# Logic_Module_-_Power_V7_2.net
KiCad netlist of a schematic drawn in EAGLE
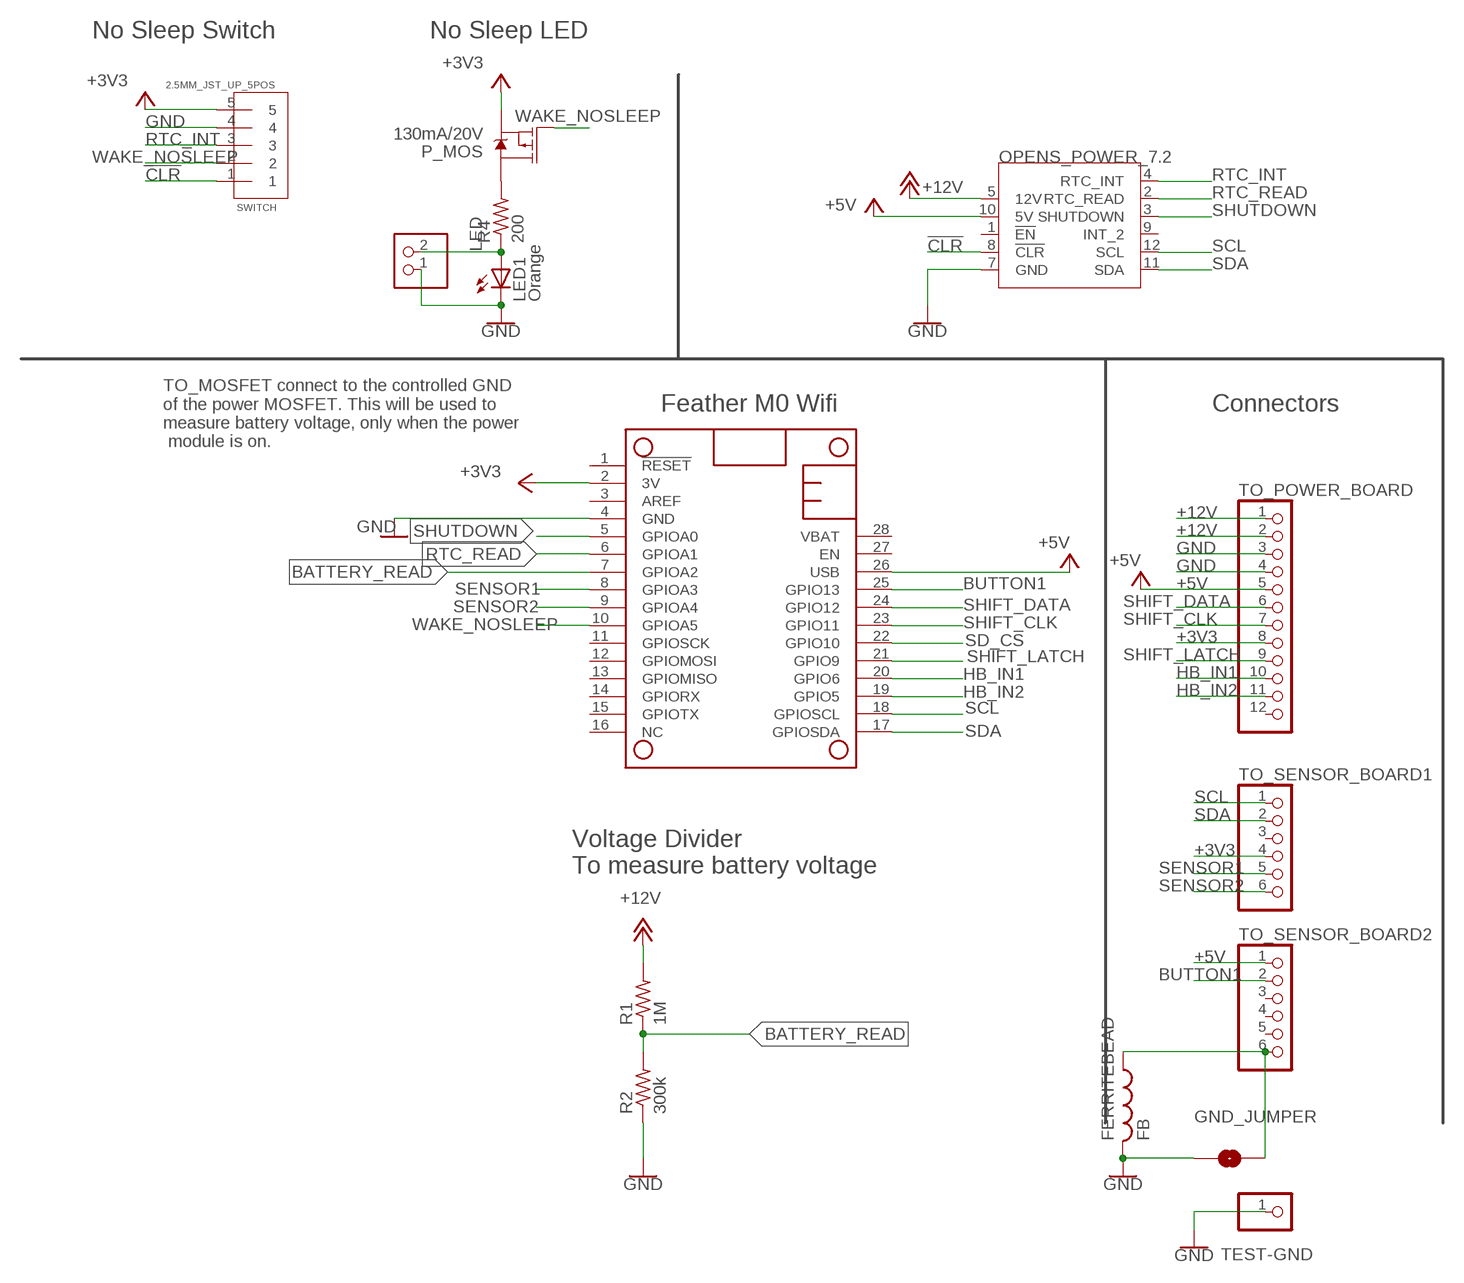
[diagram p0: schematic, sheet 1]

(export (version "E")
  (design (tool "Eeschema 10.0.6"))
  (components
    (comp (ref "FERRITEBEAD")
      (value "FB")
      (footprint "eagle-import:FB")
      (libsource (lib "eagle-import") (part "FB"))
    )
    (comp (ref "GND_JUMPER")
      (value "JUMPER-SMT_2_NO_NO-SILK")
      (footprint "eagle-import:SMT-JUMPER_2_NO_NO-SILK")
      (libsource (lib "eagle-import") (part "JUMPER-SMT_2_NO_NO-SILK"))
    )
    (comp (ref "LED")
      (value "2.5MM_JST_UP_2POS")
      (footprint "eagle-import:JST_2POS_2.5MM_UP")
      (libsource (lib "eagle-import") (part "2.5MM_JST_UP_2POS"))
    )
    (comp (ref "LED1")
      (value "Orange")
      (footprint "eagle-import:LED3MM")
      (libsource (lib "eagle-import") (part "LED3MM"))
    )
    (comp (ref "MS1")
      (value "FEATHERWING")
      (footprint "eagle-import:FEATHERWING")
      (libsource (lib "eagle-import") (part "FEATHERWING"))
    )
    (comp (ref "P_MOS")
      (value "130mA/20V")
      (footprint "eagle-import:SOT23-3")
      (libsource (lib "eagle-import") (part "MOSFET_PCH-IRLML2244"))
    )
    (comp (ref "R1")
      (value "1M")
      (footprint "eagle-import:R1206")
      (libsource (lib "eagle-import") (part "R-US_R1206"))
    )
    (comp (ref "R2")
      (value "300k")
      (footprint "eagle-import:R1206")
      (libsource (lib "eagle-import") (part "R-US_R1206"))
    )
    (comp (ref "R4")
      (value "200")
      (footprint "eagle-import:0204_7")
      (libsource (lib "eagle-import") (part "R-US_0204/7"))
    )
    (comp (ref "SWITCH")
      (value "2.5MM_JST_UP_5POS")
      (footprint "eagle-import:JST_5POS_2.5MM_UP")
      (libsource (lib "eagle-import") (part "2.5MM_JST_UP_5POS"))
    )
    (comp (ref "TEST-GND")
      (value "PINHD-1X1")
      (footprint "eagle-import:1X01")
      (libsource (lib "eagle-import") (part "PINHD-1X1"))
    )
    (comp (ref "TO_POWER_BOARD")
      (value "PINHD-1X12")
      (footprint "eagle-import:1X12")
      (libsource (lib "eagle-import") (part "PINHD-1X12"))
    )
    (comp (ref "TO_SENSOR_BOARD1")
      (value "PINHD-1X6CB")
      (footprint "eagle-import:1X06-CLEANBIG")
      (libsource (lib "eagle-import") (part "PINHD-1X6CB"))
    )
    (comp (ref "TO_SENSOR_BOARD2")
      (value "PINHD-1X6CB")
      (footprint "eagle-import:1X06-CLEANBIG")
      (libsource (lib "eagle-import") (part "PINHD-1X6CB"))
    )
    (comp (ref "U$1")
      (value "OPENS_POWER_7.2")
      (footprint "eagle-import:OPENS_POWER_7.2")
      (libsource (lib "eagle-import") (part "OPENS_POWER_7.2"))
    )
  )
  (nets
    (net (code "1") (name "+3V3") (class "Default")
      (node (ref "MS1") (pin "2") (pinfunction "3V_2") (pintype "power_in"))
      (node (ref "P_MOS") (pin "2") (pinfunction "S_2") (pintype "bidirectional"))
      (node (ref "SWITCH") (pin "5") (pinfunction "5_5") (pintype "bidirectional"))
      (node (ref "TO_POWER_BOARD") (pin "8") (pinfunction "8_8") (pintype "passive"))
      (node (ref "TO_SENSOR_BOARD1") (pin "4") (pinfunction "4_4") (pintype "passive"))
    )
    (net (code "2") (name "+5V") (class "Default")
      (node (ref "MS1") (pin "26") (pinfunction "USB_26") (pintype "power_in"))
      (node (ref "TO_POWER_BOARD") (pin "5") (pinfunction "5_5") (pintype "passive"))
      (node (ref "TO_SENSOR_BOARD2") (pin "1") (pinfunction "1_1") (pintype "passive"))
      (node (ref "U$1") (pin "10") (pinfunction "5V_10") (pintype "bidirectional"))
    )
    (net (code "3") (name "+12V") (class "Default")
      (node (ref "R1") (pin "2") (pinfunction "2_2") (pintype "passive"))
      (node (ref "TO_POWER_BOARD") (pin "1") (pinfunction "1_1") (pintype "passive"))
      (node (ref "TO_POWER_BOARD") (pin "2") (pinfunction "2_2") (pintype "passive"))
      (node (ref "U$1") (pin "5") (pinfunction "12V_5") (pintype "bidirectional"))
    )
    (net (code "4") (name "/BUTTON1") (class "Default")
      (node (ref "MS1") (pin "25") (pinfunction "GPIO13_25") (pintype "bidirectional"))
      (node (ref "TO_SENSOR_BOARD2") (pin "2") (pinfunction "2_2") (pintype "passive"))
    )
    (net (code "5") (name "/HB_IN1") (class "Default")
      (node (ref "MS1") (pin "20") (pinfunction "GPIO6_20") (pintype "bidirectional"))
      (node (ref "TO_POWER_BOARD") (pin "10") (pinfunction "10_10") (pintype "passive"))
    )
    (net (code "6") (name "/HB_IN2") (class "Default")
      (node (ref "MS1") (pin "19") (pinfunction "GPIO5_19") (pintype "bidirectional"))
      (node (ref "TO_POWER_BOARD") (pin "11") (pinfunction "11_11") (pintype "passive"))
    )
    (net (code "7") (name "/RTC_INT") (class "Default")
      (node (ref "SWITCH") (pin "3") (pinfunction "3_3") (pintype "bidirectional"))
      (node (ref "U$1") (pin "4") (pinfunction "RTC_INT_4") (pintype "bidirectional"))
    )
    (net (code "8") (name "/SCL") (class "Default")
      (node (ref "MS1") (pin "18") (pinfunction "GPIOSCL_18") (pintype "bidirectional"))
      (node (ref "TO_SENSOR_BOARD1") (pin "1") (pinfunction "1_1") (pintype "passive"))
      (node (ref "U$1") (pin "12") (pinfunction "SCL_12") (pintype "bidirectional"))
    )
    (net (code "9") (name "/SDA") (class "Default")
      (node (ref "MS1") (pin "17") (pinfunction "GPIOSDA_17") (pintype "bidirectional"))
      (node (ref "TO_SENSOR_BOARD1") (pin "2") (pinfunction "2_2") (pintype "passive"))
      (node (ref "U$1") (pin "11") (pinfunction "SDA_11") (pintype "bidirectional"))
    )
    (net (code "10") (name "/SD_CS") (class "Default")
      (node (ref "MS1") (pin "22") (pinfunction "GPIO10_22") (pintype "bidirectional"))
    )
    (net (code "11") (name "/SENSOR1") (class "Default")
      (node (ref "MS1") (pin "8") (pinfunction "GPIOA3_8") (pintype "bidirectional"))
      (node (ref "TO_SENSOR_BOARD1") (pin "5") (pinfunction "5_5") (pintype "passive"))
    )
    (net (code "12") (name "/SENSOR2") (class "Default")
      (node (ref "MS1") (pin "9") (pinfunction "GPIOA4_9") (pintype "bidirectional"))
      (node (ref "TO_SENSOR_BOARD1") (pin "6") (pinfunction "6_6") (pintype "passive"))
    )
    (net (code "13") (name "/SHIFT_CLK") (class "Default")
      (node (ref "MS1") (pin "23") (pinfunction "GPIO11_23") (pintype "bidirectional"))
      (node (ref "TO_POWER_BOARD") (pin "7") (pinfunction "7_7") (pintype "passive"))
    )
    (net (code "14") (name "/SHIFT_DATA") (class "Default")
      (node (ref "MS1") (pin "24") (pinfunction "GPIO12_24") (pintype "bidirectional"))
      (node (ref "TO_POWER_BOARD") (pin "6") (pinfunction "6_6") (pintype "passive"))
    )
    (net (code "15") (name "/SHIFT_LATCH") (class "Default")
      (node (ref "MS1") (pin "21") (pinfunction "GPIO9_21") (pintype "bidirectional"))
      (node (ref "TO_POWER_BOARD") (pin "9") (pinfunction "9_9") (pintype "passive"))
    )
    (net (code "16") (name "/VBAT") (class "Default")
      (node (ref "MS1") (pin "28") (pinfunction "VBAT_28") (pintype "power_in"))
    )
    (net (code "17") (name "/WAKE_NOSLEEP") (class "Default")
      (node (ref "MS1") (pin "10") (pinfunction "GPIOA5_10") (pintype "bidirectional"))
      (node (ref "P_MOS") (pin "1") (pinfunction "G_1") (pintype "bidirectional"))
      (node (ref "SWITCH") (pin "2") (pinfunction "2_2") (pintype "bidirectional"))
    )
    (net (code "18") (name "/~{CLR}") (class "Default")
      (node (ref "SWITCH") (pin "1") (pinfunction "1_1") (pintype "bidirectional"))
      (node (ref "U$1") (pin "8") (pinfunction "~{CLR}_8") (pintype "bidirectional"))
    )
    (net (code "19") (name "BATTERY_READ") (class "Default")
      (node (ref "MS1") (pin "7") (pinfunction "GPIOA2_7") (pintype "bidirectional"))
      (node (ref "R1") (pin "1") (pinfunction "1_1") (pintype "passive"))
      (node (ref "R2") (pin "2") (pinfunction "2_2") (pintype "passive"))
    )
    (net (code "20") (name "GND") (class "Default")
      (node (ref "FERRITEBEAD") (pin "P$2") (pinfunction "2_P$2") (pintype "passive"))
      (node (ref "GND_JUMPER") (pin "1") (pinfunction "1_1") (pintype "passive"))
      (node (ref "LED") (pin "1") (pinfunction "1_1") (pintype "bidirectional"))
      (node (ref "LED1") (pin "K") (pinfunction "C_K") (pintype "passive"))
      (node (ref "MS1") (pin "4") (pinfunction "GND_4") (pintype "power_in"))
      (node (ref "R2") (pin "1") (pinfunction "1_1") (pintype "passive"))
      (node (ref "SWITCH") (pin "4") (pinfunction "4_4") (pintype "bidirectional"))
      (node (ref "TEST-GND") (pin "1") (pinfunction "1_1") (pintype "passive"))
      (node (ref "TO_POWER_BOARD") (pin "3") (pinfunction "3_3") (pintype "passive"))
      (node (ref "TO_POWER_BOARD") (pin "4") (pinfunction "4_4") (pintype "passive"))
      (node (ref "U$1") (pin "7") (pinfunction "GND_7") (pintype "bidirectional"))
    )
    (net (code "21") (name "Net-(FERRITEBEAD-1)") (class "Default")
      (node (ref "FERRITEBEAD") (pin "P$1") (pinfunction "1_P$1") (pintype "passive"))
      (node (ref "GND_JUMPER") (pin "2") (pinfunction "2_2") (pintype "passive"))
      (node (ref "TO_SENSOR_BOARD2") (pin "6") (pinfunction "6_6") (pintype "passive"))
    )
    (net (code "22") (name "Net-(LED-Pad2)") (class "Default")
      (node (ref "LED") (pin "2") (pinfunction "2_2") (pintype "bidirectional"))
      (node (ref "LED1") (pin "A") (pinfunction "A_A") (pintype "passive"))
      (node (ref "R4") (pin "1") (pinfunction "1_1") (pintype "passive"))
    )
    (net (code "23") (name "Net-(P_MOS-D)") (class "Default")
      (node (ref "P_MOS") (pin "3") (pinfunction "D_3") (pintype "bidirectional"))
      (node (ref "R4") (pin "2") (pinfunction "2_2") (pintype "passive"))
    )
    (net (code "24") (name "RTC_READ") (class "Default")
      (node (ref "MS1") (pin "6") (pinfunction "GPIOA1_6") (pintype "bidirectional"))
      (node (ref "U$1") (pin "2") (pinfunction "RTC_READ_2") (pintype "bidirectional"))
    )
    (net (code "25") (name "SHUTDOWN") (class "Default")
      (node (ref "MS1") (pin "5") (pinfunction "GPIOA0_5") (pintype "bidirectional"))
      (node (ref "U$1") (pin "3") (pinfunction "SHUTDOWN_3") (pintype "bidirectional"))
    )
    (net (code "26") (name "unconnected-(MS1-AREF-Pad3)") (class "Default")
      (node (ref "MS1") (pin "3") (pinfunction "AREF_3") (pintype "passive"))
    )
    (net (code "27") (name "unconnected-(MS1-EN-Pad27)") (class "Default")
      (node (ref "MS1") (pin "27") (pinfunction "EN_27") (pintype "passive"))
    )
    (net (code "28") (name "unconnected-(MS1-GPIOMISO-Pad13)") (class "Default")
      (node (ref "MS1") (pin "13") (pinfunction "GPIOMISO_13") (pintype "bidirectional"))
    )
    (net (code "29") (name "unconnected-(MS1-GPIOMOSI-Pad12)") (class "Default")
      (node (ref "MS1") (pin "12") (pinfunction "GPIOMOSI_12") (pintype "bidirectional"))
    )
    (net (code "30") (name "unconnected-(MS1-GPIORX-Pad14)") (class "Default")
      (node (ref "MS1") (pin "14") (pinfunction "GPIORX_14") (pintype "bidirectional"))
    )
    (net (code "31") (name "unconnected-(MS1-GPIOSCK-Pad11)") (class "Default")
      (node (ref "MS1") (pin "11") (pinfunction "GPIOSCK_11") (pintype "bidirectional"))
    )
    (net (code "32") (name "unconnected-(MS1-GPIOTX-Pad15)") (class "Default")
      (node (ref "MS1") (pin "15") (pinfunction "GPIOTX_15") (pintype "bidirectional"))
    )
    (net (code "33") (name "unconnected-(MS1-NC-Pad16)") (class "Default")
      (node (ref "MS1") (pin "16") (pinfunction "NC_16") (pintype "passive"))
    )
    (net (code "34") (name "unconnected-(MS1-~{RESET}-Pad1)") (class "Default")
      (node (ref "MS1") (pin "1") (pinfunction "~{RESET}_1") (pintype "input"))
    )
    (net (code "35") (name "unconnected-(TO_POWER_BOARD-Pad12)") (class "Default")
      (node (ref "TO_POWER_BOARD") (pin "12") (pinfunction "12_12") (pintype "passive"))
    )
    (net (code "36") (name "unconnected-(TO_SENSOR_BOARD1-Pad3)") (class "Default")
      (node (ref "TO_SENSOR_BOARD1") (pin "3") (pinfunction "3_3") (pintype "passive"))
    )
    (net (code "37") (name "unconnected-(TO_SENSOR_BOARD2-Pad3)") (class "Default")
      (node (ref "TO_SENSOR_BOARD2") (pin "3") (pinfunction "3_3") (pintype "passive"))
    )
    (net (code "38") (name "unconnected-(TO_SENSOR_BOARD2-Pad4)") (class "Default")
      (node (ref "TO_SENSOR_BOARD2") (pin "4") (pinfunction "4_4") (pintype "passive"))
    )
    (net (code "39") (name "unconnected-(TO_SENSOR_BOARD2-Pad5)") (class "Default")
      (node (ref "TO_SENSOR_BOARD2") (pin "5") (pinfunction "5_5") (pintype "passive"))
    )
    (net (code "40") (name "unconnected-(U$1-INT_2-Pad9)") (class "Default")
      (node (ref "U$1") (pin "9") (pinfunction "INT_2_9") (pintype "bidirectional"))
    )
    (net (code "41") (name "unconnected-(U$1-~{EN}-Pad1)") (class "Default")
      (node (ref "U$1") (pin "1") (pinfunction "~{EN}_1") (pintype "bidirectional"))
    )
  )
)
